# CurrentShuntAmp2.net
KiCad netlist of a schematic drawn in Altium Designer
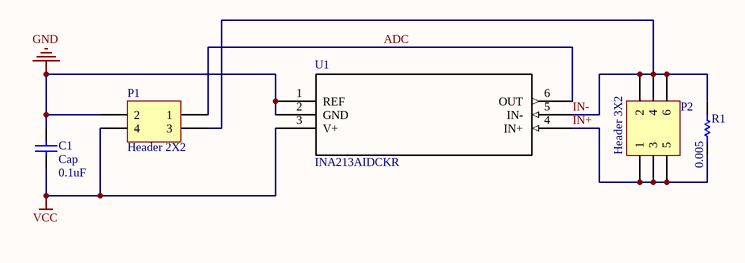
[diagram p0: CurrentShuntAmp2.SchDoc]

(export (version "E")
  (design (tool "Eeschema 10.0.6"))
  (components
    (comp (ref "C1")
      (value "Cap")
      (footprint "1608[0603]")
      (description "Capacitor (Semiconductor SIM Model)")
      (fields (field (name "ALTIUM_VALUE") "0.1uF") (field (name "PUBLISHER") "Altium Limited"))
      (libsource (lib "Miscellaneous Devices") (part "Cap Semi"))
    )
    (comp (ref "P1")
      (value "Header 2X2")
      (footprint "HDR2X2")
      (description "Header, 2-Pin, Dual row")
      (fields (field (name "PUBLISHER") "Altium Limited"))
      (libsource (lib "Miscellaneous Connectors") (part "Header 2X2"))
    )
    (comp (ref "P2")
      (value "Header 3X2")
      (footprint "HDR2X3")
      (description "Header, 3-Pin, Dual row")
      (fields (field (name "PUBLISHER") "Altium Limited"))
      (libsource (lib "Miscellaneous Connectors") (part "Header 3X2"))
    )
    (comp (ref "R1")
      (value "0.005")
      (footprint "C1206")
      (description "Resistor")
      (fields (field (name "Comment") "Res1") (field (name "PUBLISHER") "Altium Limited"))
      (libsource (lib "Miscellaneous Devices") (part "Res1"))
    )
    (comp (ref "U1")
      (value "INA213AIDCKR")
      (footprint "DCK6")
      (description "Imported")
      (fields
        (field (name "MANUFACTURER") "Texas Instruments")
        (field (name "GENERIC_PART_NUMBER") "INA213A-Q1")
      )
      (libsource (lib "Schlib") (part "INA213AIDCKR"))
    )
  )
  (nets
    (net (code "1") (name "/ADC") (class "Default")
      (node (ref "P1") (pin "1") (pinfunction "1_1") (pintype "passive"))
      (node (ref "U1") (pin "6") (pinfunction "OUT_6") (pintype "output"))
    )
    (net (code "2") (name "/IN+") (class "Default")
      (node (ref "P2") (pin "1") (pinfunction "1_1") (pintype "passive"))
      (node (ref "P2") (pin "3") (pinfunction "3_3") (pintype "passive"))
      (node (ref "P2") (pin "5") (pinfunction "5_5") (pintype "passive"))
      (node (ref "R1") (pin "1") (pinfunction "1_1") (pintype "passive"))
      (node (ref "U1") (pin "4") (pinfunction "IN+_4") (pintype "input"))
    )
    (net (code "3") (name "/IN-") (class "Default")
      (node (ref "P1") (pin "3") (pinfunction "3_3") (pintype "passive"))
      (node (ref "P2") (pin "2") (pinfunction "2_2") (pintype "passive"))
      (node (ref "P2") (pin "4") (pinfunction "4_4") (pintype "passive"))
      (node (ref "P2") (pin "6") (pinfunction "6_6") (pintype "passive"))
      (node (ref "R1") (pin "2") (pinfunction "2_2") (pintype "passive"))
      (node (ref "U1") (pin "5") (pinfunction "IN-_5") (pintype "input"))
    )
    (net (code "4") (name "GND") (class "Default")
      (node (ref "C1") (pin "2") (pinfunction "2_2") (pintype "passive"))
      (node (ref "P1") (pin "2") (pinfunction "2_2") (pintype "passive"))
      (node (ref "U1") (pin "1") (pinfunction "REF_1") (pintype "power_in"))
      (node (ref "U1") (pin "2") (pinfunction "GND_2") (pintype "power_in"))
    )
    (net (code "5") (name "VCC") (class "Default")
      (node (ref "C1") (pin "1") (pinfunction "1_1") (pintype "passive"))
      (node (ref "P1") (pin "4") (pinfunction "4_4") (pintype "passive"))
      (node (ref "U1") (pin "3") (pinfunction "V+_3") (pintype "power_in"))
    )
  )
)
